# Connectors.net
KiCad netlist of a schematic drawn in Altium Designer
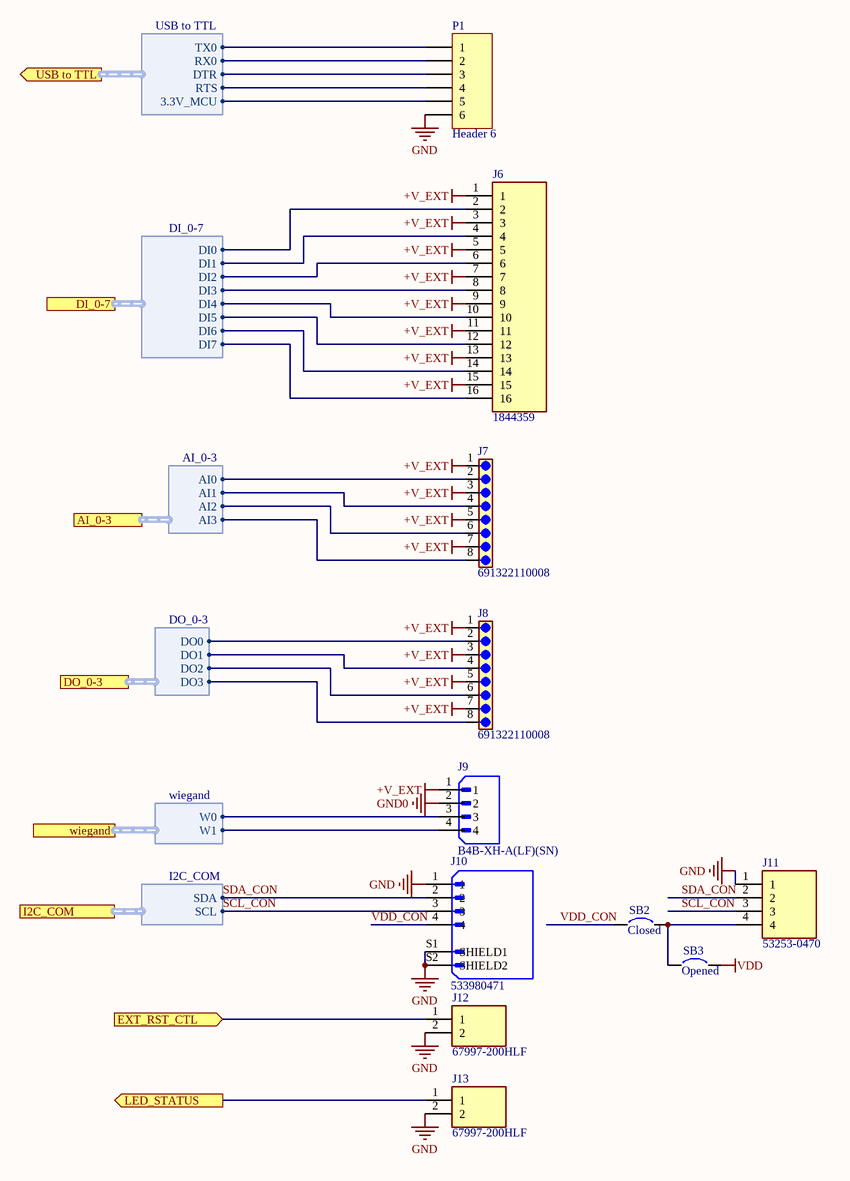
[diagram p0: Connectors.SchDoc]

(export (version "E")
  (design (tool "Eeschema 10.0.6"))
  (components
    (comp (ref "J6")
      (value "1844359")
      (footprint "SamacSys:1844359")
      (description "Connector")
      (fields (field (name "MOUSER PART NUMBER") "651-1844359"))
      (libsource (lib "*") (part "1844359"))
    )
    (comp (ref "J7")
      (value "691322110008")
      (footprint "691322110008")
      (fields (field (name "MF") "Wurth Electronics"))
      (libsource (lib "691322110008") (part "691322110008"))
    )
    (comp (ref "J8")
      (value "691322110008")
      (footprint "691322110008")
      (fields (field (name "MF") "Wurth Electronics"))
      (libsource (lib "ESP32_IO_module") (part "691322110008"))
    )
    (comp (ref "J9")
      (value "B4B-XH-A(LF)(SN)")
      (footprint "JST_B4B-XH-A(LF)(SN)")
      (description "Connector Header Through Hole 4 position 0.098 (2.50mm)")
      (fields (field (name "MF") "JST Sales"))
      (libsource (lib "B4B-XH-A_LF__SN_") (part "B4B-XH-A(LF)(SN)"))
    )
    (comp (ref "J10")
      (value "533980471")
      (footprint "MOLEX_533980471")
      (description "Conn Shrouded Header (3 Sides) HDR 4 POS 1.25mm Solder ST Top Entry SMD PicoBladeâ„¢ T/R")
      (fields (field (name "MF") "Molex") (field (name "DIGI-KEY_PART_NUMBER") "WM7608TR-ND"))
      (libsource (lib "533980471") (part "533980471"))
    )
    (comp (ref "J11")
      (value "53253-0470")
      (footprint "SHDR4W50P0X200_1X4_1000X365X550P")
      (description "Connector")
      (fields (field (name "MOUSER PART NUMBER") "538-53253-0470"))
      (libsource (lib "ESP32_IO_module") (part "53253-0470"))
    )
    (comp (ref "J12")
      (value "67997-200HLF")
      (footprint "SamacSys:HDRV2W67P254_2X1_254X483X858P")
      (description "Connector")
      (fields (field (name "MOUSER PART NUMBER") "649-67997-200HLF"))
      (libsource (lib "SamacSys") (part "67997-200HLF"))
    )
    (comp (ref "J13")
      (value "67997-200HLF")
      (footprint "SamacSys:HDRV2W67P254_2X1_254X483X858P")
      (description "Connector")
      (fields (field (name "MOUSER PART NUMBER") "649-67997-200HLF"))
      (libsource (lib "SamacSys") (part "67997-200HLF"))
    )
    (comp (ref "P1")
      (value "Header 6")
      (footprint "HDR1X6")
      (description "Header, 6-Pin")
      (fields (field (name "PUBLISHER") "Altium Limited"))
      (libsource (lib "Miscellaneous Connectors") (part "Header 6"))
    )
    (comp (ref "SB2")
      (value "Closed")
      (footprint "SB_0603")
      (description "Circuit Breaker")
      (fields (field (name "PUBLISHER") "Altium Limited"))
      (libsource (lib "IIOT_GATEWAY_MT7621") (part "Circuit Breaker_close"))
    )
    (comp (ref "SB3")
      (value "Opened")
      (footprint "SB_0603")
      (description "Circuit Breaker")
      (fields (field (name "PUBLISHER") "Altium Limited"))
      (libsource (lib "IIOT_GATEWAY_MT7621") (part "Circuit Breaker_close"))
    )
  )
  (nets
    (net (code "9") (name "+V_EXT") (class "Default")
      (node (ref "J6") (pin "1") (pinfunction "1_1") (pintype "passive"))
      (node (ref "J6") (pin "11") (pinfunction "11_11") (pintype "passive"))
      (node (ref "J6") (pin "13") (pinfunction "13_13") (pintype "passive"))
      (node (ref "J6") (pin "15") (pinfunction "15_15") (pintype "passive"))
      (node (ref "J6") (pin "3") (pinfunction "3_3") (pintype "passive"))
      (node (ref "J6") (pin "5") (pinfunction "5_5") (pintype "passive"))
      (node (ref "J6") (pin "7") (pinfunction "7_7") (pintype "passive"))
      (node (ref "J6") (pin "9") (pinfunction "9_9") (pintype "passive"))
      (node (ref "J7") (pin "1") (pinfunction "1_1") (pintype "passive"))
      (node (ref "J7") (pin "3") (pinfunction "3_3") (pintype "passive"))
      (node (ref "J7") (pin "5") (pinfunction "5_5") (pintype "passive"))
      (node (ref "J7") (pin "7") (pinfunction "7_7") (pintype "passive"))
      (node (ref "J8") (pin "1") (pinfunction "1_1") (pintype "passive"))
      (node (ref "J8") (pin "3") (pinfunction "3_3") (pintype "passive"))
      (node (ref "J8") (pin "5") (pinfunction "5_5") (pintype "passive"))
      (node (ref "J8") (pin "7") (pinfunction "7_7") (pintype "passive"))
      (node (ref "J9") (pin "1") (pinfunction "1_1") (pintype "passive"))
    )
    (net (code "10") (name "/3.3V_MCU") (class "Default")
      (node (ref "P1") (pin "5") (pinfunction "5_5") (pintype "passive"))
    )
    (net (code "11") (name "/AI0") (class "Default")
      (node (ref "J7") (pin "2") (pinfunction "2_2") (pintype "passive"))
    )
    (net (code "12") (name "/AI1") (class "Default")
      (node (ref "J7") (pin "4") (pinfunction "4_4") (pintype "passive"))
    )
    (net (code "13") (name "/AI2") (class "Default")
      (node (ref "J7") (pin "6") (pinfunction "6_6") (pintype "passive"))
    )
    (net (code "14") (name "/AI3") (class "Default")
      (node (ref "J7") (pin "8") (pinfunction "8_8") (pintype "passive"))
    )
    (net (code "15") (name "/DI0") (class "Default")
      (node (ref "J6") (pin "2") (pinfunction "2_2") (pintype "passive"))
    )
    (net (code "16") (name "/DI1") (class "Default")
      (node (ref "J6") (pin "4") (pinfunction "4_4") (pintype "passive"))
    )
    (net (code "17") (name "/DI2") (class "Default")
      (node (ref "J6") (pin "6") (pinfunction "6_6") (pintype "passive"))
    )
    (net (code "18") (name "/DI3") (class "Default")
      (node (ref "J6") (pin "8") (pinfunction "8_8") (pintype "passive"))
    )
    (net (code "19") (name "/DI4") (class "Default")
      (node (ref "J6") (pin "10") (pinfunction "10_10") (pintype "passive"))
    )
    (net (code "20") (name "/DI5") (class "Default")
      (node (ref "J6") (pin "12") (pinfunction "12_12") (pintype "passive"))
    )
    (net (code "21") (name "/DI6") (class "Default")
      (node (ref "J6") (pin "14") (pinfunction "14_14") (pintype "passive"))
    )
    (net (code "22") (name "/DI7") (class "Default")
      (node (ref "J6") (pin "16") (pinfunction "16_16") (pintype "passive"))
    )
    (net (code "23") (name "/DO0") (class "Default")
      (node (ref "J8") (pin "2") (pinfunction "2_2") (pintype "passive"))
    )
    (net (code "24") (name "/DO1") (class "Default")
      (node (ref "J8") (pin "4") (pinfunction "4_4") (pintype "passive"))
    )
    (net (code "25") (name "/DO2") (class "Default")
      (node (ref "J8") (pin "6") (pinfunction "6_6") (pintype "passive"))
    )
    (net (code "26") (name "/DO3") (class "Default")
      (node (ref "J8") (pin "8") (pinfunction "8_8") (pintype "passive"))
    )
    (net (code "27") (name "/DTR") (class "Default")
      (node (ref "P1") (pin "3") (pinfunction "3_3") (pintype "passive"))
    )
    (net (code "28") (name "/EXT_RST_CTL") (class "Default")
      (node (ref "J12") (pin "1") (pinfunction "1_1") (pintype "passive"))
    )
    (net (code "29") (name "/LED_STATUS") (class "Default")
      (node (ref "J13") (pin "1") (pinfunction "1_1") (pintype "passive"))
    )
    (net (code "30") (name "/RTS") (class "Default")
      (node (ref "P1") (pin "4") (pinfunction "4_4") (pintype "passive"))
    )
    (net (code "31") (name "/RX0") (class "Default")
      (node (ref "P1") (pin "2") (pinfunction "2_2") (pintype "passive"))
    )
    (net (code "32") (name "/SCL_CON") (class "Default")
      (node (ref "J10") (pin "3") (pinfunction "3_3") (pintype "passive"))
      (node (ref "J11") (pin "3") (pinfunction "3_3") (pintype "passive"))
    )
    (net (code "33") (name "/SDA_CON") (class "Default")
      (node (ref "J10") (pin "2") (pinfunction "2_2") (pintype "passive"))
      (node (ref "J11") (pin "2") (pinfunction "2_2") (pintype "passive"))
    )
    (net (code "34") (name "/TX0") (class "Default")
      (node (ref "P1") (pin "1") (pinfunction "1_1") (pintype "passive"))
    )
    (net (code "35") (name "/VDD_CON") (class "Default")
      (node (ref "J10") (pin "4") (pinfunction "4_4") (pintype "passive"))
      (node (ref "SB2") (pin "1") (pinfunction "1_1") (pintype "passive"))
    )
    (net (code "36") (name "/W0") (class "Default")
      (node (ref "J9") (pin "3") (pinfunction "3_3") (pintype "passive"))
    )
    (net (code "37") (name "/W1") (class "Default")
      (node (ref "J9") (pin "4") (pinfunction "4_4") (pintype "passive"))
    )
    (net (code "44") (name "GND") (class "Default")
      (node (ref "J10") (pin "1") (pinfunction "1_1") (pintype "passive"))
      (node (ref "J10") (pin "S1") (pinfunction "SHIELD1_S1") (pintype "passive"))
      (node (ref "J10") (pin "S2") (pinfunction "SHIELD2_S2") (pintype "passive"))
      (node (ref "J11") (pin "1") (pinfunction "1_1") (pintype "passive"))
      (node (ref "J12") (pin "2") (pinfunction "2_2") (pintype "passive"))
      (node (ref "J13") (pin "2") (pinfunction "2_2") (pintype "passive"))
      (node (ref "P1") (pin "6") (pinfunction "6_6") (pintype "passive"))
    )
    (net (code "45") (name "GND0") (class "Default")
      (node (ref "J9") (pin "2") (pinfunction "2_2") (pintype "passive"))
    )
    (net (code "46") (name "Net-(J11-Pad4)") (class "Default")
      (node (ref "J11") (pin "4") (pinfunction "4_4") (pintype "passive"))
      (node (ref "SB2") (pin "2") (pinfunction "2_2") (pintype "passive"))
      (node (ref "SB3") (pin "1") (pinfunction "1_1") (pintype "passive"))
    )
    (net (code "47") (name "VDD") (class "Default")
      (node (ref "SB3") (pin "2") (pinfunction "2_2") (pintype "passive"))
    )
  )
)
